# FlightComputer_PDB.net
KiCad netlist of a schematic drawn in EAGLE
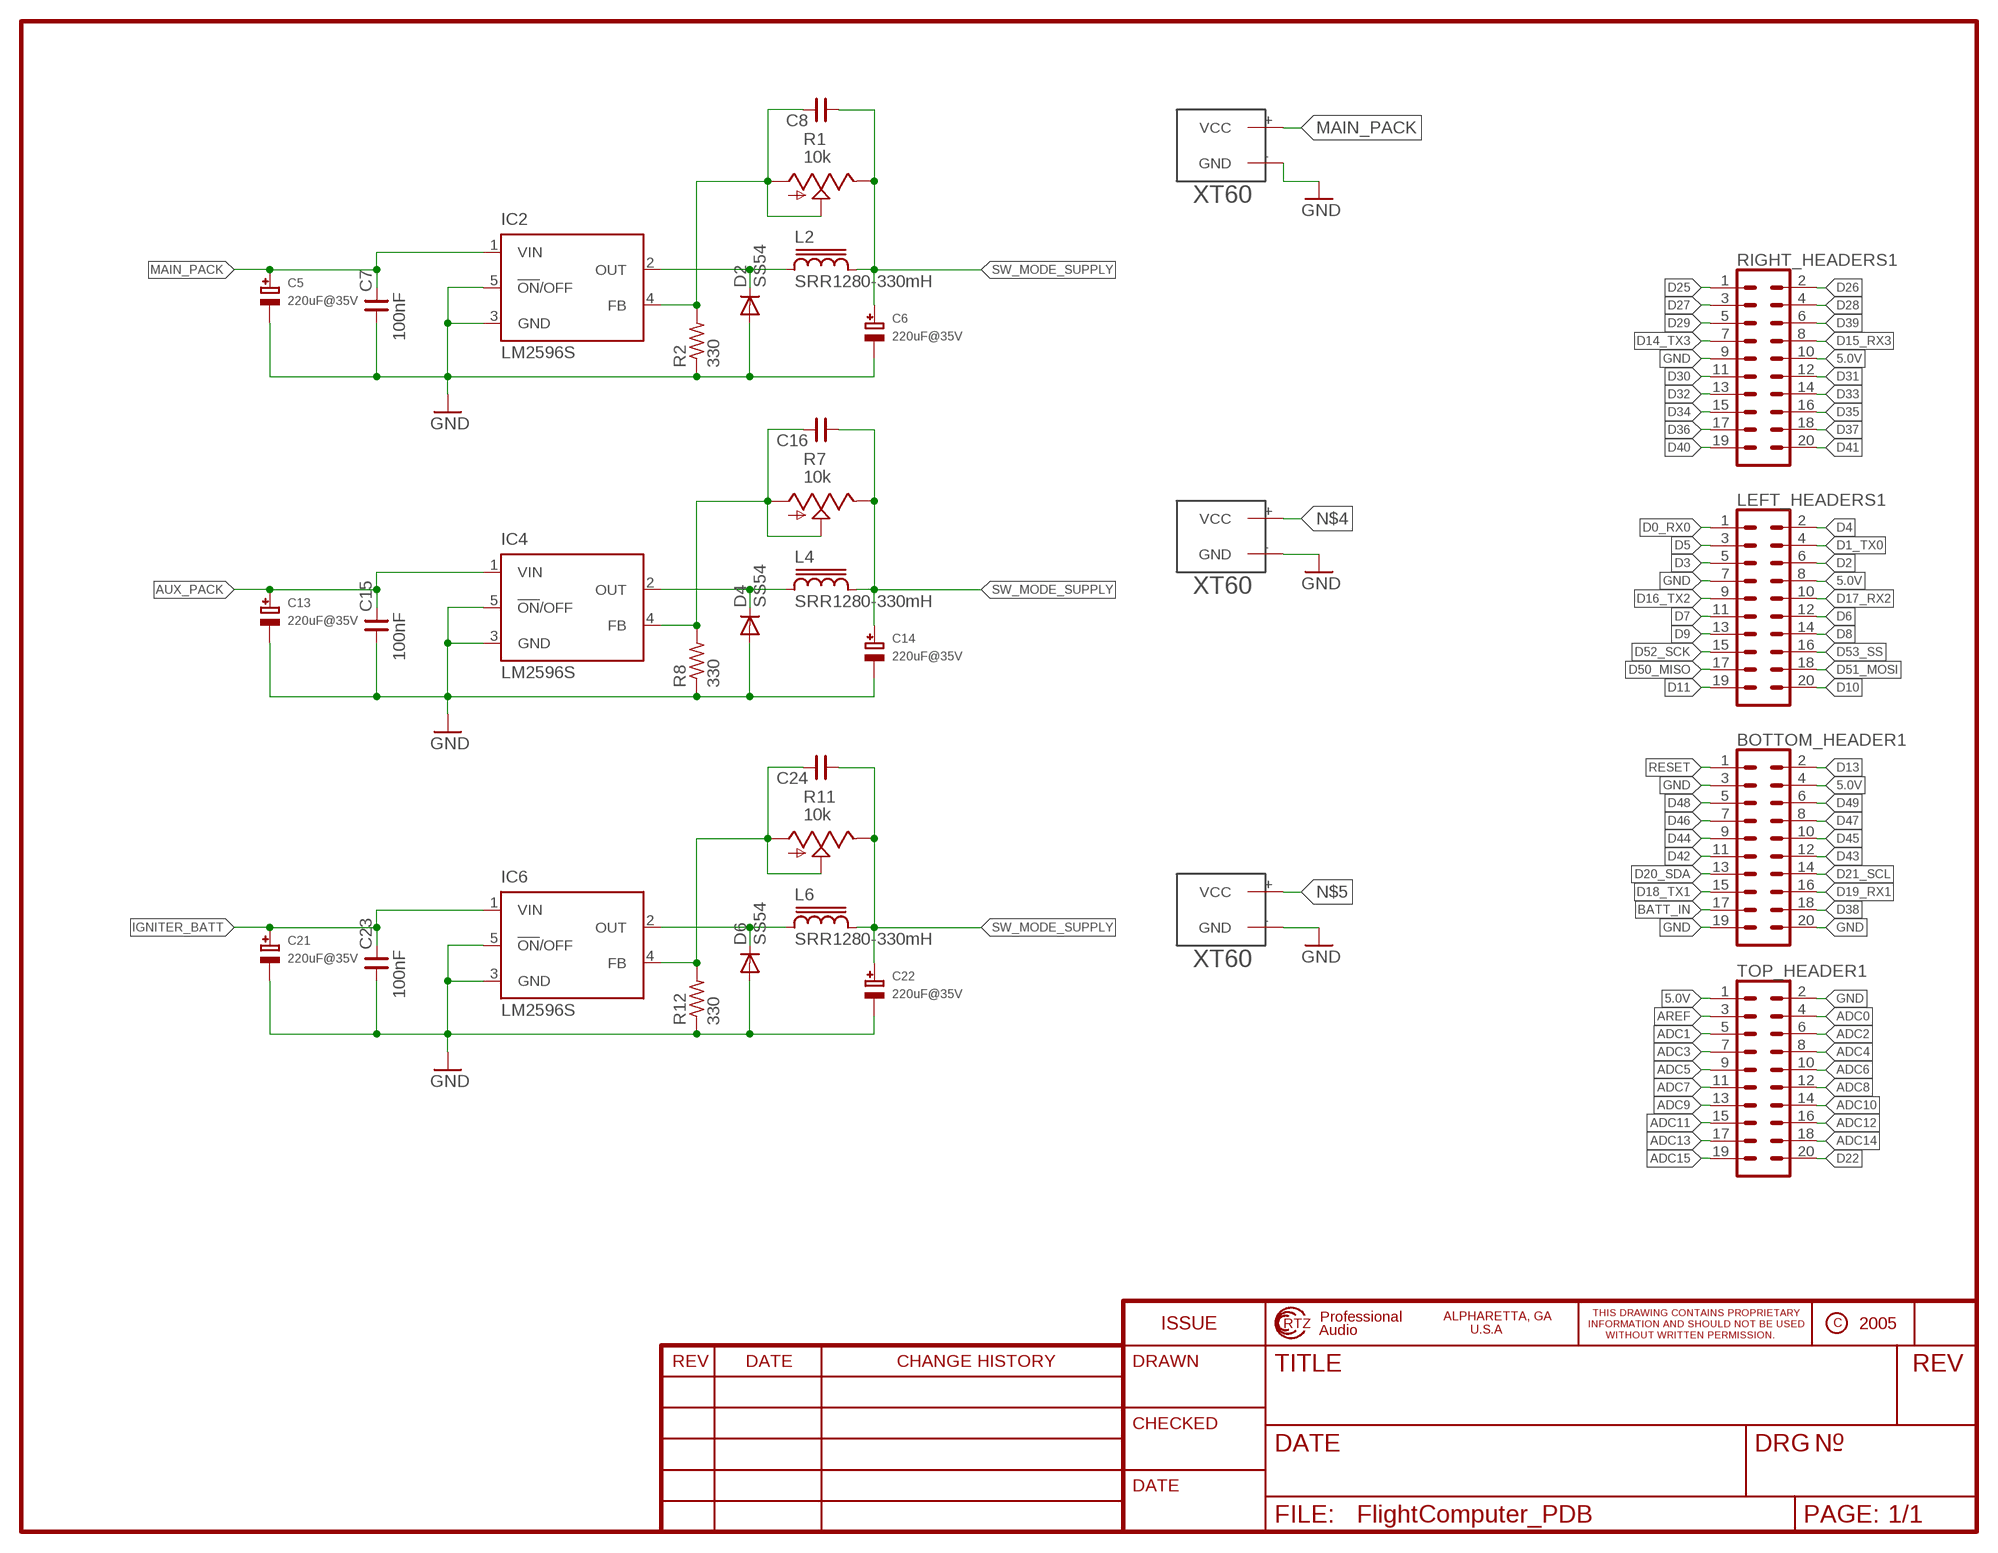
[diagram p0: schematic, sheet 1]

(export (version "E")
  (design (tool "Eeschema 10.0.6"))
  (components
    (comp (ref "BOTTOM_HEADER1")
      (value "CONN_10X2")
      (footprint "eagle-import:2X10")
      (libsource (lib "eagle-import") (part "CONN_10X2"))
    )
    (comp (ref "C5")
      (value "220uF@35V")
      (footprint "eagle-import:PANASONIC_D")
      (libsource (lib "eagle-import") (part "CAP_ELECTROLYTICPANASONIC_D"))
    )
    (comp (ref "C6")
      (value "220uF@35V")
      (footprint "eagle-import:PANASONIC_D")
      (libsource (lib "eagle-import") (part "CAP_ELECTROLYTICPANASONIC_D"))
    )
    (comp (ref "C7")
      (value "100nF")
      (footprint "eagle-import:0603")
      (libsource (lib "eagle-import") (part "CNP-0603"))
    )
    (comp (ref "C8")
      (value "CNP-0603")
      (footprint "eagle-import:0603")
      (libsource (lib "eagle-import") (part "CNP-0603"))
    )
    (comp (ref "C13")
      (value "220uF@35V")
      (footprint "eagle-import:PANASONIC_D")
      (libsource (lib "eagle-import") (part "CAP_ELECTROLYTICPANASONIC_D"))
    )
    (comp (ref "C14")
      (value "220uF@35V")
      (footprint "eagle-import:PANASONIC_D")
      (libsource (lib "eagle-import") (part "CAP_ELECTROLYTICPANASONIC_D"))
    )
    (comp (ref "C15")
      (value "100nF")
      (footprint "eagle-import:0603")
      (libsource (lib "eagle-import") (part "CNP-0603"))
    )
    (comp (ref "C16")
      (value "CNP-0603")
      (footprint "eagle-import:0603")
      (libsource (lib "eagle-import") (part "CNP-0603"))
    )
    (comp (ref "C21")
      (value "220uF@35V")
      (footprint "eagle-import:PANASONIC_D")
      (libsource (lib "eagle-import") (part "CAP_ELECTROLYTICPANASONIC_D"))
    )
    (comp (ref "C22")
      (value "220uF@35V")
      (footprint "eagle-import:PANASONIC_D")
      (libsource (lib "eagle-import") (part "CAP_ELECTROLYTICPANASONIC_D"))
    )
    (comp (ref "C23")
      (value "100nF")
      (footprint "eagle-import:0603")
      (libsource (lib "eagle-import") (part "CNP-0603"))
    )
    (comp (ref "C24")
      (value "CNP-0603")
      (footprint "eagle-import:0603")
      (libsource (lib "eagle-import") (part "CNP-0603"))
    )
    (comp (ref "D2")
      (value "SS54")
      (footprint "eagle-import:DO214AB")
      (fields (field (name "MF") "Fairchild") (field (name "MPN") "S3G"))
      (libsource (lib "eagle-import") (part "S3G"))
    )
    (comp (ref "D4")
      (value "SS54")
      (footprint "eagle-import:DO214AB")
      (fields (field (name "MF") "Fairchild") (field (name "MPN") "S3G"))
      (libsource (lib "eagle-import") (part "S3G"))
    )
    (comp (ref "D6")
      (value "SS54")
      (footprint "eagle-import:DO214AB")
      (fields (field (name "MF") "Fairchild") (field (name "MPN") "S3G"))
      (libsource (lib "eagle-import") (part "S3G"))
    )
    (comp (ref "IC2")
      (value "LM2596S")
      (footprint "eagle-import:TO263-5")
      (fields (field (name "MF") "NATIONAL SEMICONDUCTOR") (field (name "MPN") "LM2596S-ADJ/NOPB"))
      (libsource (lib "eagle-import") (part "LM2596S"))
    )
    (comp (ref "IC4")
      (value "LM2596S")
      (footprint "eagle-import:TO263-5")
      (fields (field (name "MF") "NATIONAL SEMICONDUCTOR") (field (name "MPN") "LM2596S-ADJ/NOPB"))
      (libsource (lib "eagle-import") (part "LM2596S"))
    )
    (comp (ref "IC6")
      (value "LM2596S")
      (footprint "eagle-import:TO263-5")
      (fields (field (name "MF") "NATIONAL SEMICONDUCTOR") (field (name "MPN") "LM2596S-ADJ/NOPB"))
      (libsource (lib "eagle-import") (part "LM2596S"))
    )
    (comp (ref "L2")
      (value "SRR1280-330mH")
      (footprint "eagle-import:SRR1280")
      (libsource (lib "eagle-import") (part "SRR1280"))
    )
    (comp (ref "L4")
      (value "SRR1280-330mH")
      (footprint "eagle-import:SRR1280")
      (libsource (lib "eagle-import") (part "SRR1280"))
    )
    (comp (ref "L6")
      (value "SRR1280-330mH")
      (footprint "eagle-import:SRR1280")
      (libsource (lib "eagle-import") (part "SRR1280"))
    )
    (comp (ref "LEFT_HEADERS1")
      (value "CONN_10X2")
      (footprint "eagle-import:2X10")
      (libsource (lib "eagle-import") (part "CONN_10X2"))
    )
    (comp (ref "R1")
      (value "10k")
      (footprint "eagle-import:S64W")
      (libsource (lib "eagle-import") (part "TRIM_US-S64W"))
    )
    (comp (ref "R2")
      (value "330")
      (footprint "eagle-import:R0603")
      (libsource (lib "eagle-import") (part "R-US_R0603"))
    )
    (comp (ref "R7")
      (value "10k")
      (footprint "eagle-import:S64W")
      (libsource (lib "eagle-import") (part "TRIM_US-S64W"))
    )
    (comp (ref "R8")
      (value "330")
      (footprint "eagle-import:R0603")
      (libsource (lib "eagle-import") (part "R-US_R0603"))
    )
    (comp (ref "R11")
      (value "10k")
      (footprint "eagle-import:S64W")
      (libsource (lib "eagle-import") (part "TRIM_US-S64W"))
    )
    (comp (ref "R12")
      (value "330")
      (footprint "eagle-import:R0603")
      (libsource (lib "eagle-import") (part "R-US_R0603"))
    )
    (comp (ref "RIGHT_HEADERS1")
      (value "CONN_10X2")
      (footprint "eagle-import:2X10")
      (libsource (lib "eagle-import") (part "CONN_10X2"))
    )
    (comp (ref "TOP_HEADER1")
      (value "CONN_10X2")
      (footprint "eagle-import:2X10")
      (libsource (lib "eagle-import") (part "CONN_10X2"))
    )
    (comp (ref "U$1")
      (value "XT60")
      (footprint "eagle-import:XT60")
      (libsource (lib "eagle-import") (part "XT60"))
    )
    (comp (ref "U$2")
      (value "XT60")
      (footprint "eagle-import:XT60")
      (libsource (lib "eagle-import") (part "XT60"))
    )
    (comp (ref "U$3")
      (value "XT60")
      (footprint "eagle-import:XT60")
      (libsource (lib "eagle-import") (part "XT60"))
    )
  )
  (nets
    (net (code "1") (name "5.0V") (class "Default")
      (node (ref "BOTTOM_HEADER1") (pin "4") (pinfunction "4_4") (pintype "passive"))
      (node (ref "LEFT_HEADERS1") (pin "8") (pinfunction "8_8") (pintype "passive"))
      (node (ref "RIGHT_HEADERS1") (pin "10") (pinfunction "10_10") (pintype "passive"))
      (node (ref "TOP_HEADER1") (pin "1") (pinfunction "1_1") (pintype "passive"))
    )
    (net (code "2") (name "ADC0") (class "Default")
      (node (ref "TOP_HEADER1") (pin "4") (pinfunction "4_4") (pintype "passive"))
    )
    (net (code "3") (name "ADC1") (class "Default")
      (node (ref "TOP_HEADER1") (pin "5") (pinfunction "5_5") (pintype "passive"))
    )
    (net (code "4") (name "ADC2") (class "Default")
      (node (ref "TOP_HEADER1") (pin "6") (pinfunction "6_6") (pintype "passive"))
    )
    (net (code "5") (name "ADC3") (class "Default")
      (node (ref "TOP_HEADER1") (pin "7") (pinfunction "7_7") (pintype "passive"))
    )
    (net (code "6") (name "ADC4") (class "Default")
      (node (ref "TOP_HEADER1") (pin "8") (pinfunction "8_8") (pintype "passive"))
    )
    (net (code "7") (name "ADC5") (class "Default")
      (node (ref "TOP_HEADER1") (pin "9") (pinfunction "9_9") (pintype "passive"))
    )
    (net (code "8") (name "ADC6") (class "Default")
      (node (ref "TOP_HEADER1") (pin "10") (pinfunction "10_10") (pintype "passive"))
    )
    (net (code "9") (name "ADC7") (class "Default")
      (node (ref "TOP_HEADER1") (pin "11") (pinfunction "11_11") (pintype "passive"))
    )
    (net (code "10") (name "ADC8") (class "Default")
      (node (ref "TOP_HEADER1") (pin "12") (pinfunction "12_12") (pintype "passive"))
    )
    (net (code "11") (name "ADC9") (class "Default")
      (node (ref "TOP_HEADER1") (pin "13") (pinfunction "13_13") (pintype "passive"))
    )
    (net (code "12") (name "ADC10") (class "Default")
      (node (ref "TOP_HEADER1") (pin "14") (pinfunction "14_14") (pintype "passive"))
    )
    (net (code "13") (name "ADC11") (class "Default")
      (node (ref "TOP_HEADER1") (pin "15") (pinfunction "15_15") (pintype "passive"))
    )
    (net (code "14") (name "ADC12") (class "Default")
      (node (ref "TOP_HEADER1") (pin "16") (pinfunction "16_16") (pintype "passive"))
    )
    (net (code "15") (name "ADC13") (class "Default")
      (node (ref "TOP_HEADER1") (pin "17") (pinfunction "17_17") (pintype "passive"))
    )
    (net (code "16") (name "ADC14") (class "Default")
      (node (ref "TOP_HEADER1") (pin "18") (pinfunction "18_18") (pintype "passive"))
    )
    (net (code "17") (name "ADC15") (class "Default")
      (node (ref "TOP_HEADER1") (pin "19") (pinfunction "19_19") (pintype "passive"))
    )
    (net (code "18") (name "AREF") (class "Default")
      (node (ref "TOP_HEADER1") (pin "3") (pinfunction "3_3") (pintype "passive"))
    )
    (net (code "19") (name "AUX_PACK") (class "Default")
      (node (ref "C13") (pin "+") (pinfunction "+_+") (pintype "passive"))
      (node (ref "C15") (pin "2") (pinfunction "2_2") (pintype "passive"))
      (node (ref "IC4") (pin "1") (pinfunction "VIN_1") (pintype "input"))
    )
    (net (code "20") (name "BATT_IN") (class "Default")
      (node (ref "BOTTOM_HEADER1") (pin "17") (pinfunction "17_17") (pintype "passive"))
    )
    (net (code "21") (name "D0_RX0") (class "Default")
      (node (ref "LEFT_HEADERS1") (pin "1") (pinfunction "1_1") (pintype "passive"))
    )
    (net (code "22") (name "D1_TX0") (class "Default")
      (node (ref "LEFT_HEADERS1") (pin "4") (pinfunction "4_4") (pintype "passive"))
    )
    (net (code "23") (name "D2") (class "Default")
      (node (ref "LEFT_HEADERS1") (pin "6") (pinfunction "6_6") (pintype "passive"))
    )
    (net (code "24") (name "D3") (class "Default")
      (node (ref "LEFT_HEADERS1") (pin "5") (pinfunction "5_5") (pintype "passive"))
    )
    (net (code "25") (name "D4") (class "Default")
      (node (ref "LEFT_HEADERS1") (pin "2") (pinfunction "2_2") (pintype "passive"))
    )
    (net (code "26") (name "D5") (class "Default")
      (node (ref "LEFT_HEADERS1") (pin "3") (pinfunction "3_3") (pintype "passive"))
    )
    (net (code "27") (name "D6") (class "Default")
      (node (ref "LEFT_HEADERS1") (pin "12") (pinfunction "12_12") (pintype "passive"))
    )
    (net (code "28") (name "D7") (class "Default")
      (node (ref "LEFT_HEADERS1") (pin "11") (pinfunction "11_11") (pintype "passive"))
    )
    (net (code "29") (name "D8") (class "Default")
      (node (ref "LEFT_HEADERS1") (pin "14") (pinfunction "14_14") (pintype "passive"))
    )
    (net (code "30") (name "D9") (class "Default")
      (node (ref "LEFT_HEADERS1") (pin "13") (pinfunction "13_13") (pintype "passive"))
    )
    (net (code "31") (name "D10") (class "Default")
      (node (ref "LEFT_HEADERS1") (pin "20") (pinfunction "20_20") (pintype "passive"))
    )
    (net (code "32") (name "D11") (class "Default")
      (node (ref "LEFT_HEADERS1") (pin "19") (pinfunction "19_19") (pintype "passive"))
    )
    (net (code "33") (name "D13") (class "Default")
      (node (ref "BOTTOM_HEADER1") (pin "2") (pinfunction "2_2") (pintype "passive"))
    )
    (net (code "34") (name "D14_TX3") (class "Default")
      (node (ref "RIGHT_HEADERS1") (pin "7") (pinfunction "7_7") (pintype "passive"))
    )
    (net (code "35") (name "D15_RX3") (class "Default")
      (node (ref "RIGHT_HEADERS1") (pin "8") (pinfunction "8_8") (pintype "passive"))
    )
    (net (code "36") (name "D16_TX2") (class "Default")
      (node (ref "LEFT_HEADERS1") (pin "9") (pinfunction "9_9") (pintype "passive"))
    )
    (net (code "37") (name "D17_RX2") (class "Default")
      (node (ref "LEFT_HEADERS1") (pin "10") (pinfunction "10_10") (pintype "passive"))
    )
    (net (code "38") (name "D18_TX1") (class "Default")
      (node (ref "BOTTOM_HEADER1") (pin "15") (pinfunction "15_15") (pintype "passive"))
    )
    (net (code "39") (name "D19_RX1") (class "Default")
      (node (ref "BOTTOM_HEADER1") (pin "16") (pinfunction "16_16") (pintype "passive"))
    )
    (net (code "40") (name "D20_SDA") (class "Default")
      (node (ref "BOTTOM_HEADER1") (pin "13") (pinfunction "13_13") (pintype "passive"))
    )
    (net (code "41") (name "D21_SCL") (class "Default")
      (node (ref "BOTTOM_HEADER1") (pin "14") (pinfunction "14_14") (pintype "passive"))
    )
    (net (code "42") (name "D22") (class "Default")
      (node (ref "TOP_HEADER1") (pin "20") (pinfunction "20_20") (pintype "passive"))
    )
    (net (code "43") (name "D25") (class "Default")
      (node (ref "RIGHT_HEADERS1") (pin "1") (pinfunction "1_1") (pintype "passive"))
    )
    (net (code "44") (name "D26") (class "Default")
      (node (ref "RIGHT_HEADERS1") (pin "2") (pinfunction "2_2") (pintype "passive"))
    )
    (net (code "45") (name "D27") (class "Default")
      (node (ref "RIGHT_HEADERS1") (pin "3") (pinfunction "3_3") (pintype "passive"))
    )
    (net (code "46") (name "D28") (class "Default")
      (node (ref "RIGHT_HEADERS1") (pin "4") (pinfunction "4_4") (pintype "passive"))
    )
    (net (code "47") (name "D29") (class "Default")
      (node (ref "RIGHT_HEADERS1") (pin "5") (pinfunction "5_5") (pintype "passive"))
    )
    (net (code "48") (name "D30") (class "Default")
      (node (ref "RIGHT_HEADERS1") (pin "11") (pinfunction "11_11") (pintype "passive"))
    )
    (net (code "49") (name "D31") (class "Default")
      (node (ref "RIGHT_HEADERS1") (pin "12") (pinfunction "12_12") (pintype "passive"))
    )
    (net (code "50") (name "D32") (class "Default")
      (node (ref "RIGHT_HEADERS1") (pin "13") (pinfunction "13_13") (pintype "passive"))
    )
    (net (code "51") (name "D33") (class "Default")
      (node (ref "RIGHT_HEADERS1") (pin "14") (pinfunction "14_14") (pintype "passive"))
    )
    (net (code "52") (name "D34") (class "Default")
      (node (ref "RIGHT_HEADERS1") (pin "15") (pinfunction "15_15") (pintype "passive"))
    )
    (net (code "53") (name "D35") (class "Default")
      (node (ref "RIGHT_HEADERS1") (pin "16") (pinfunction "16_16") (pintype "passive"))
    )
    (net (code "54") (name "D36") (class "Default")
      (node (ref "RIGHT_HEADERS1") (pin "17") (pinfunction "17_17") (pintype "passive"))
    )
    (net (code "55") (name "D37") (class "Default")
      (node (ref "RIGHT_HEADERS1") (pin "18") (pinfunction "18_18") (pintype "passive"))
    )
    (net (code "56") (name "D38") (class "Default")
      (node (ref "BOTTOM_HEADER1") (pin "18") (pinfunction "18_18") (pintype "passive"))
    )
    (net (code "57") (name "D39") (class "Default")
      (node (ref "RIGHT_HEADERS1") (pin "6") (pinfunction "6_6") (pintype "passive"))
    )
    (net (code "58") (name "D40") (class "Default")
      (node (ref "RIGHT_HEADERS1") (pin "19") (pinfunction "19_19") (pintype "passive"))
    )
    (net (code "59") (name "D41") (class "Default")
      (node (ref "RIGHT_HEADERS1") (pin "20") (pinfunction "20_20") (pintype "passive"))
    )
    (net (code "60") (name "D42") (class "Default")
      (node (ref "BOTTOM_HEADER1") (pin "11") (pinfunction "11_11") (pintype "passive"))
    )
    (net (code "61") (name "D43") (class "Default")
      (node (ref "BOTTOM_HEADER1") (pin "12") (pinfunction "12_12") (pintype "passive"))
    )
    (net (code "62") (name "D44") (class "Default")
      (node (ref "BOTTOM_HEADER1") (pin "9") (pinfunction "9_9") (pintype "passive"))
    )
    (net (code "63") (name "D45") (class "Default")
      (node (ref "BOTTOM_HEADER1") (pin "10") (pinfunction "10_10") (pintype "passive"))
    )
    (net (code "64") (name "D46") (class "Default")
      (node (ref "BOTTOM_HEADER1") (pin "7") (pinfunction "7_7") (pintype "passive"))
    )
    (net (code "65") (name "D47") (class "Default")
      (node (ref "BOTTOM_HEADER1") (pin "8") (pinfunction "8_8") (pintype "passive"))
    )
    (net (code "66") (name "D48") (class "Default")
      (node (ref "BOTTOM_HEADER1") (pin "5") (pinfunction "5_5") (pintype "passive"))
    )
    (net (code "67") (name "D49") (class "Default")
      (node (ref "BOTTOM_HEADER1") (pin "6") (pinfunction "6_6") (pintype "passive"))
    )
    (net (code "68") (name "D50_MISO") (class "Default")
      (node (ref "LEFT_HEADERS1") (pin "17") (pinfunction "17_17") (pintype "passive"))
    )
    (net (code "69") (name "D51_MOSI") (class "Default")
      (node (ref "LEFT_HEADERS1") (pin "18") (pinfunction "18_18") (pintype "passive"))
    )
    (net (code "70") (name "D52_SCK") (class "Default")
      (node (ref "LEFT_HEADERS1") (pin "15") (pinfunction "15_15") (pintype "passive"))
    )
    (net (code "71") (name "D53_SS") (class "Default")
      (node (ref "LEFT_HEADERS1") (pin "16") (pinfunction "16_16") (pintype "passive"))
    )
    (net (code "72") (name "GND") (class "Default")
      (node (ref "BOTTOM_HEADER1") (pin "19") (pinfunction "19_19") (pintype "passive"))
      (node (ref "BOTTOM_HEADER1") (pin "20") (pinfunction "20_20") (pintype "passive"))
      (node (ref "BOTTOM_HEADER1") (pin "3") (pinfunction "3_3") (pintype "passive"))
      (node (ref "C13") (pin "-") (pinfunction "-_-") (pintype "passive"))
      (node (ref "C14") (pin "-") (pinfunction "-_-") (pintype "passive"))
      (node (ref "C15") (pin "1") (pinfunction "1_1") (pintype "passive"))
      (node (ref "C21") (pin "-") (pinfunction "-_-") (pintype "passive"))
      (node (ref "C22") (pin "-") (pinfunction "-_-") (pintype "passive"))
      (node (ref "C23") (pin "1") (pinfunction "1_1") (pintype "passive"))
      (node (ref "C5") (pin "-") (pinfunction "-_-") (pintype "passive"))
      (node (ref "C6") (pin "-") (pinfunction "-_-") (pintype "passive"))
      (node (ref "C7") (pin "1") (pinfunction "1_1") (pintype "passive"))
      (node (ref "D2") (pin "A") (pinfunction "A_A") (pintype "passive"))
      (node (ref "D4") (pin "A") (pinfunction "A_A") (pintype "passive"))
      (node (ref "D6") (pin "A") (pinfunction "A_A") (pintype "passive"))
      (node (ref "IC2") (pin "3") (pinfunction "GND_3") (pintype "power_in"))
      (node (ref "IC2") (pin "5") (pinfunction "~{ON}/OFF_5") (pintype "input"))
      (node (ref "IC4") (pin "3") (pinfunction "GND_3") (pintype "power_in"))
      (node (ref "IC4") (pin "5") (pinfunction "~{ON}/OFF_5") (pintype "input"))
      (node (ref "IC6") (pin "3") (pinfunction "GND_3") (pintype "power_in"))
      (node (ref "IC6") (pin "5") (pinfunction "~{ON}/OFF_5") (pintype "input"))
      (node (ref "LEFT_HEADERS1") (pin "7") (pinfunction "7_7") (pintype "passive"))
      (node (ref "R12") (pin "1") (pinfunction "1_1") (pintype "passive"))
      (node (ref "R2") (pin "1") (pinfunction "1_1") (pintype "passive"))
      (node (ref "R8") (pin "1") (pinfunction "1_1") (pintype "passive"))
      (node (ref "RIGHT_HEADERS1") (pin "9") (pinfunction "9_9") (pintype "passive"))
      (node (ref "TOP_HEADER1") (pin "2") (pinfunction "2_2") (pintype "passive"))
      (node (ref "U$1") (pin "-") (pinfunction "GND_-") (pintype "bidirectional"))
      (node (ref "U$2") (pin "-") (pinfunction "GND_-") (pintype "bidirectional"))
      (node (ref "U$3") (pin "-") (pinfunction "GND_-") (pintype "bidirectional"))
    )
    (net (code "73") (name "IGNITER_BATT") (class "Default")
      (node (ref "C21") (pin "+") (pinfunction "+_+") (pintype "passive"))
      (node (ref "C23") (pin "2") (pinfunction "2_2") (pintype "passive"))
      (node (ref "IC6") (pin "1") (pinfunction "VIN_1") (pintype "input"))
    )
    (net (code "74") (name "MAIN_PACK") (class "Default")
      (node (ref "C5") (pin "+") (pinfunction "+_+") (pintype "passive"))
      (node (ref "C7") (pin "2") (pinfunction "2_2") (pintype "passive"))
      (node (ref "IC2") (pin "1") (pinfunction "VIN_1") (pintype "input"))
      (node (ref "U$1") (pin "+") (pinfunction "VCC_+") (pintype "bidirectional"))
    )
    (net (code "75") (name "N$4") (class "Default")
      (node (ref "U$2") (pin "+") (pinfunction "VCC_+") (pintype "bidirectional"))
    )
    (net (code "76") (name "N$5") (class "Default")
      (node (ref "U$3") (pin "+") (pinfunction "VCC_+") (pintype "bidirectional"))
    )
    (net (code "77") (name "Net-(IC2-FB)") (class "Default")
      (node (ref "C8") (pin "2") (pinfunction "2_2") (pintype "passive"))
      (node (ref "IC2") (pin "4") (pinfunction "FB_4") (pintype "input"))
      (node (ref "R1") (pin "A") (pinfunction "A_A") (pintype "passive"))
      (node (ref "R1") (pin "S") (pinfunction "S_S") (pintype "passive"))
      (node (ref "R2") (pin "2") (pinfunction "2_2") (pintype "passive"))
    )
    (net (code "78") (name "Net-(IC2-OUT)") (class "Default")
      (node (ref "D2") (pin "C") (pinfunction "C_C") (pintype "passive"))
      (node (ref "IC2") (pin "2") (pinfunction "OUT_2") (pintype "output"))
      (node (ref "L2") (pin "1") (pinfunction "1_1") (pintype "passive"))
    )
    (net (code "79") (name "Net-(IC4-FB)") (class "Default")
      (node (ref "C16") (pin "2") (pinfunction "2_2") (pintype "passive"))
      (node (ref "IC4") (pin "4") (pinfunction "FB_4") (pintype "input"))
      (node (ref "R7") (pin "A") (pinfunction "A_A") (pintype "passive"))
      (node (ref "R7") (pin "S") (pinfunction "S_S") (pintype "passive"))
      (node (ref "R8") (pin "2") (pinfunction "2_2") (pintype "passive"))
    )
    (net (code "80") (name "Net-(IC4-OUT)") (class "Default")
      (node (ref "D4") (pin "C") (pinfunction "C_C") (pintype "passive"))
      (node (ref "IC4") (pin "2") (pinfunction "OUT_2") (pintype "output"))
      (node (ref "L4") (pin "1") (pinfunction "1_1") (pintype "passive"))
    )
    (net (code "81") (name "Net-(IC6-FB)") (class "Default")
      (node (ref "C24") (pin "2") (pinfunction "2_2") (pintype "passive"))
      (node (ref "IC6") (pin "4") (pinfunction "FB_4") (pintype "input"))
      (node (ref "R11") (pin "A") (pinfunction "A_A") (pintype "passive"))
      (node (ref "R11") (pin "S") (pinfunction "S_S") (pintype "passive"))
      (node (ref "R12") (pin "2") (pinfunction "2_2") (pintype "passive"))
    )
    (net (code "82") (name "Net-(IC6-OUT)") (class "Default")
      (node (ref "D6") (pin "C") (pinfunction "C_C") (pintype "passive"))
      (node (ref "IC6") (pin "2") (pinfunction "OUT_2") (pintype "output"))
      (node (ref "L6") (pin "1") (pinfunction "1_1") (pintype "passive"))
    )
    (net (code "83") (name "RESET") (class "Default")
      (node (ref "BOTTOM_HEADER1") (pin "1") (pinfunction "1_1") (pintype "passive"))
    )
    (net (code "84") (name "SW_MODE_SUPPLY") (class "Default")
      (node (ref "C14") (pin "+") (pinfunction "+_+") (pintype "passive"))
      (node (ref "C16") (pin "1") (pinfunction "1_1") (pintype "passive"))
      (node (ref "C22") (pin "+") (pinfunction "+_+") (pintype "passive"))
      (node (ref "C24") (pin "1") (pinfunction "1_1") (pintype "passive"))
      (node (ref "C6") (pin "+") (pinfunction "+_+") (pintype "passive"))
      (node (ref "C8") (pin "1") (pinfunction "1_1") (pintype "passive"))
      (node (ref "L2") (pin "2") (pinfunction "2_2") (pintype "passive"))
      (node (ref "L4") (pin "2") (pinfunction "2_2") (pintype "passive"))
      (node (ref "L6") (pin "2") (pinfunction "2_2") (pintype "passive"))
      (node (ref "R1") (pin "E") (pinfunction "E_E") (pintype "passive"))
      (node (ref "R11") (pin "E") (pinfunction "E_E") (pintype "passive"))
      (node (ref "R7") (pin "E") (pinfunction "E_E") (pintype "passive"))
    )
  )
)
